# Schemat.net
KiCad netlist of a schematic drawn in EAGLE
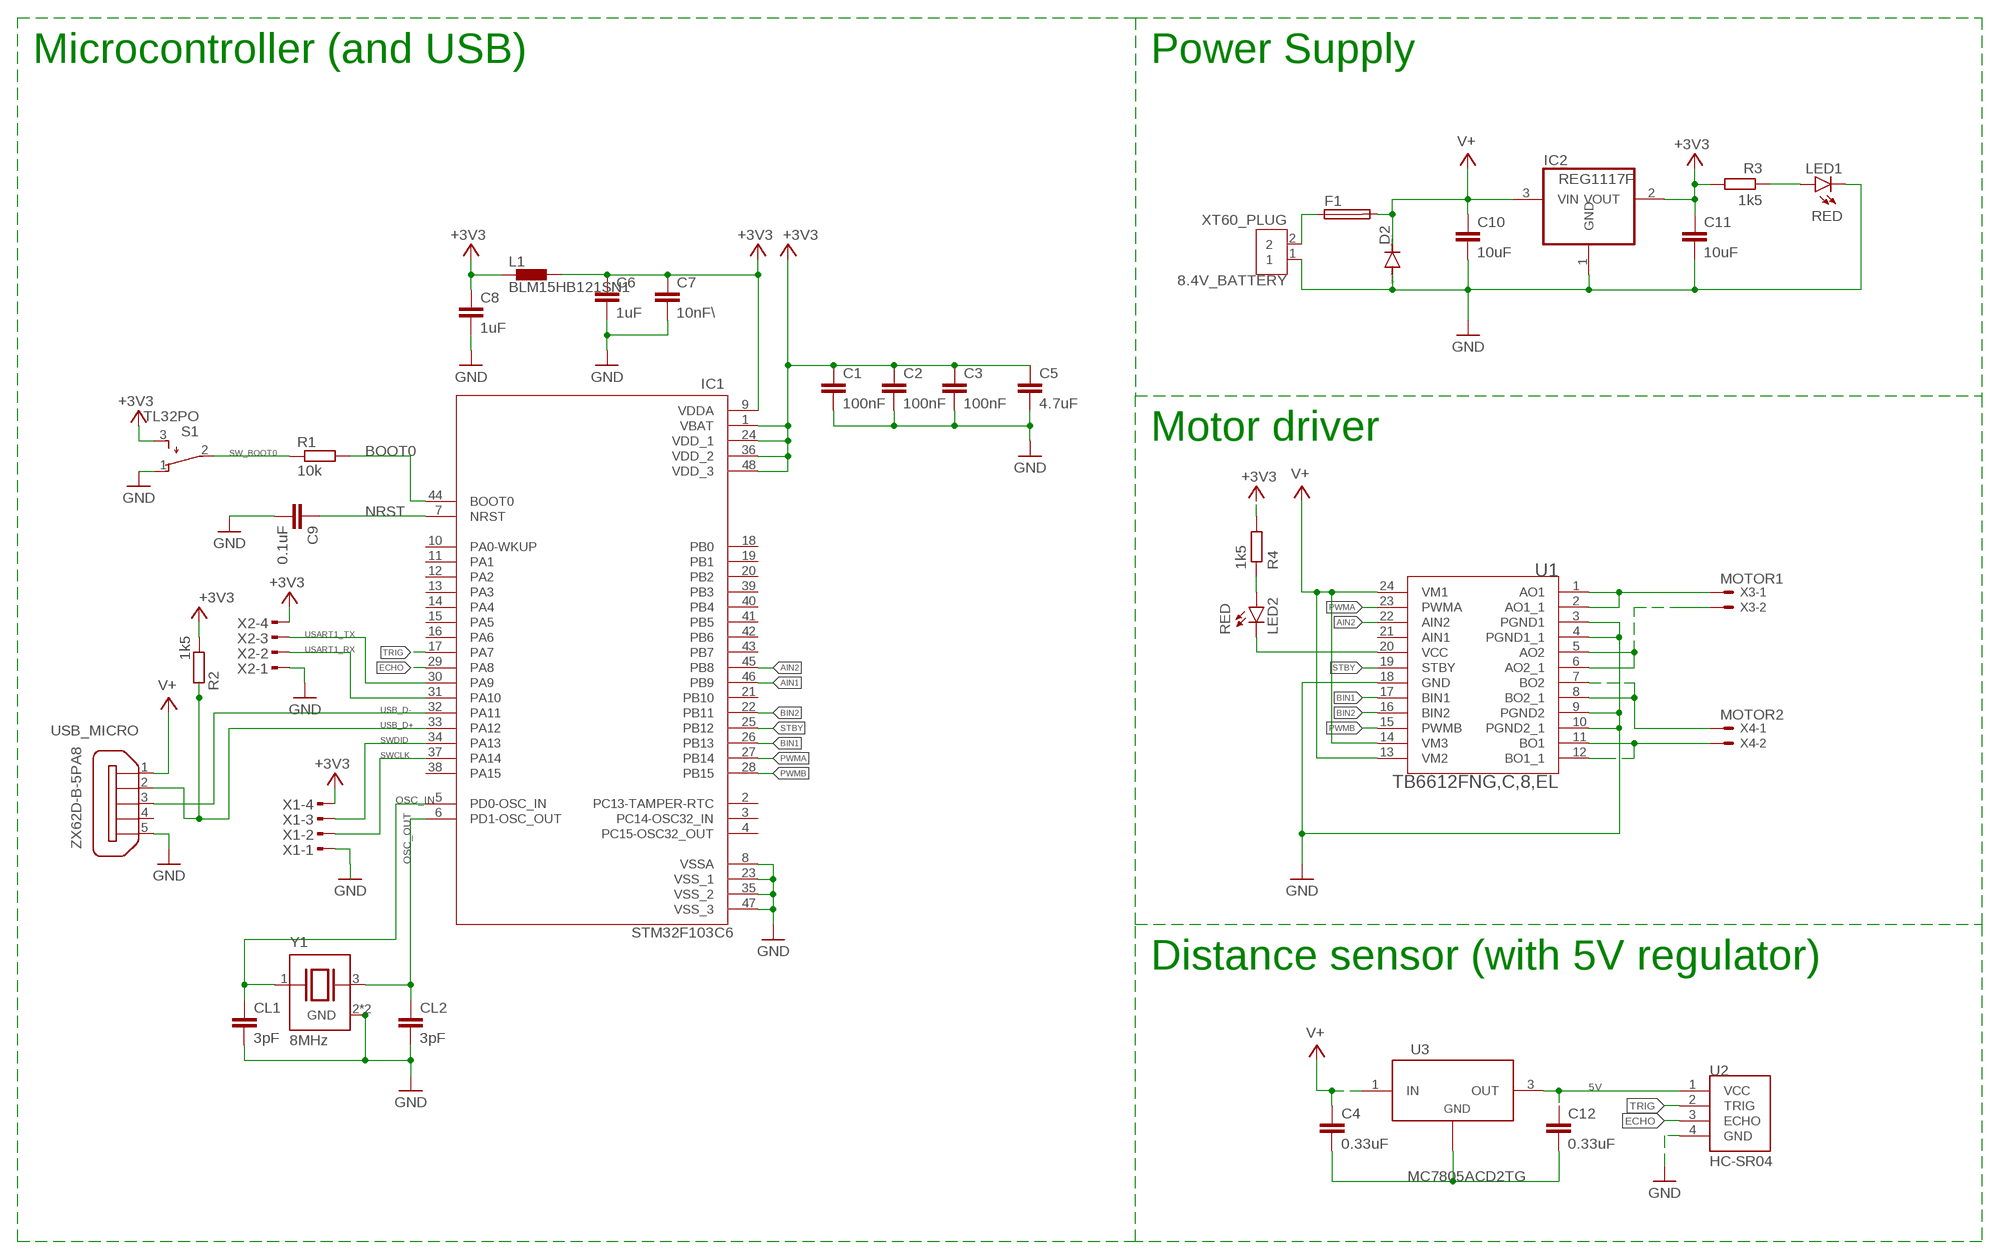
[diagram p0: schematic, sheet 1]

(export (version "E")
  (design (tool "Eeschema 10.0.6"))
  (components
    (comp (ref "8.4V_BATTERY")
      (value "XT60_PLUG")
      (footprint "eagle-import:AMASS_XT60PB-M")
      (fields (field (name "MF") "Pololu") (field (name "MP") "XT60 YELLOW"))
      (libsource (lib "eagle-import") (part "XT60_YELLOW"))
    )
    (comp (ref "C1")
      (value "100nF")
      (footprint "eagle-import:C0805")
      (libsource (lib "eagle-import") (part "C-EUC0805"))
    )
    (comp (ref "C2")
      (value "100nF")
      (footprint "eagle-import:C0805")
      (libsource (lib "eagle-import") (part "C-EUC0805"))
    )
    (comp (ref "C3")
      (value "100nF")
      (footprint "eagle-import:C0805")
      (libsource (lib "eagle-import") (part "C-EUC0805"))
    )
    (comp (ref "C4")
      (value "0.33uF")
      (footprint "eagle-import:C0805")
      (libsource (lib "eagle-import") (part "C-EUC0805"))
    )
    (comp (ref "C5")
      (value "4.7uF")
      (footprint "eagle-import:C0805")
      (libsource (lib "eagle-import") (part "C-EUC0805"))
    )
    (comp (ref "C6")
      (value "1uF")
      (footprint "eagle-import:C0805")
      (libsource (lib "eagle-import") (part "C-EUC0805"))
    )
    (comp (ref "C7")
      (value "10nF\\")
      (footprint "eagle-import:C0805")
      (libsource (lib "eagle-import") (part "C-EUC0805"))
    )
    (comp (ref "C8")
      (value "1uF")
      (footprint "eagle-import:C0805")
      (libsource (lib "eagle-import") (part "C-EUC0805"))
    )
    (comp (ref "C9")
      (value "0.1uF")
      (footprint "eagle-import:C0805")
      (libsource (lib "eagle-import") (part "C-EUC0805"))
    )
    (comp (ref "C10")
      (value "10uF")
      (footprint "eagle-import:C0805")
      (libsource (lib "eagle-import") (part "C-EUC0805"))
    )
    (comp (ref "C11")
      (value "10uF")
      (footprint "eagle-import:C0805")
      (libsource (lib "eagle-import") (part "C-EUC0805"))
    )
    (comp (ref "C12")
      (value "0.33uF")
      (footprint "eagle-import:C0805")
      (libsource (lib "eagle-import") (part "C-EUC0805"))
    )
    (comp (ref "CL1")
      (value "3pF")
      (footprint "eagle-import:C0805")
      (libsource (lib "eagle-import") (part "C-EUC0805"))
    )
    (comp (ref "CL2")
      (value "3pF")
      (footprint "eagle-import:C0805")
      (libsource (lib "eagle-import") (part "C-EUC0805"))
    )
    (comp (ref "D2")
      (value "1N4004")
      (footprint "eagle-import:DO41-10")
      (libsource (lib "eagle-import") (part "1N4004"))
    )
    (comp (ref "F1")
      (value "19559")
      (footprint "eagle-import:19559")
      (fields (field (name "MPN") "55900000001"))
      (libsource (lib "eagle-import") (part "19559"))
    )
    (comp (ref "IC1")
      (value "STM32F103C6")
      (footprint "eagle-import:QFP50P900X900X160-48N")
      (fields (field (name "MANUFACTURER") "ST Microelectronics") (field (name "MPN") "STM32F103C6T7A"))
      (libsource (lib "eagle-import") (part "STM32F103_QFP"))
    )
    (comp (ref "IC2")
      (value "REG1117F")
      (footprint "eagle-import:DD-3")
      (fields (field (name "MF") "TEXAS INSTRUMENTS") (field (name "MPN") "REG1117FAKTTT"))
      (libsource (lib "eagle-import") (part "REG1117F"))
    )
    (comp (ref "L1")
      (value "BLM15HB121SN1")
      (footprint "eagle-import:0402")
      (libsource (lib "eagle-import") (part "BLM15HB121SN1"))
    )
    (comp (ref "LED1")
      (value "RED")
      (footprint "eagle-import:LED3MM")
      (libsource (lib "eagle-import") (part "LED3MM"))
    )
    (comp (ref "LED2")
      (value "RED")
      (footprint "eagle-import:LED3MM")
      (libsource (lib "eagle-import") (part "LED3MM"))
    )
    (comp (ref "R1")
      (value "10k")
      (footprint "eagle-import:0204V")
      (libsource (lib "eagle-import") (part "R-EU_0204/2V"))
    )
    (comp (ref "R2")
      (value "1k5")
      (footprint "eagle-import:0204V")
      (libsource (lib "eagle-import") (part "R-EU_0204/2V"))
    )
    (comp (ref "R3")
      (value "1k5")
      (footprint "eagle-import:R0805")
      (libsource (lib "eagle-import") (part "R-EU_R0805"))
    )
    (comp (ref "R4")
      (value "1k5")
      (footprint "eagle-import:R0805")
      (libsource (lib "eagle-import") (part "R-EU_R0805"))
    )
    (comp (ref "S1")
      (value "TL32PO")
      (footprint "eagle-import:TL3XPO")
      (libsource (lib "eagle-import") (part "TL32PO"))
    )
    (comp (ref "U1")
      (value "TB6612FNG,C,8,EL")
      (footprint "eagle-import:SSOP-24")
      (fields
        (field (name "DIGI-KEY_PART") "TB6612FNGC8ELCT-ND")
        (field (name "MANUFACTURER") "Toshiba Semiconductor and Storage")
        (field (name "CREATED_BY") "PCBLayout.com")
      )
      (libsource (lib "eagle-import") (part "TB6612FNG,C,8,EL"))
    )
    (comp (ref "U2")
      (value "HC-SR04")
      (footprint "eagle-import:XCVR_HC-SR04")
      (fields (field (name "MF") "OSEPP Electronics"))
      (libsource (lib "eagle-import") (part "HC-SR04"))
    )
    (comp (ref "U3")
      (value "MC7805ACD2TG")
      (footprint "eagle-import:D2PAK")
      (fields
        (field (name "DIGIKEY_PART_NUMBER") "MC7805ACD2TGOS-ND")
        (field (name "MANUFACTURER") "ON Semiconductor")
        (field (name "CREATED_BY") "PCBLayout.com")
      )
      (libsource (lib "eagle-import") (part "MC7805ACD2TG"))
    )
    (comp (ref "USB_MICRO")
      (value "ZX62D-B-5PA8")
      (footprint "eagle-import:ZX62D-B-5PA8")
      (fields (field (name "MF") "Hirose"))
      (libsource (lib "eagle-import") (part "ZX62D-B-5PA8"))
    )
    (comp (ref "X1")
      (value "MTOP-4")
      (footprint "eagle-import:MTOP-4")
      (libsource (lib "eagle-import") (part "MTOP-4"))
    )
    (comp (ref "X2")
      (value "MTOP-4")
      (footprint "eagle-import:MTOP-4")
      (libsource (lib "eagle-import") (part "MTOP-4"))
    )
    (comp (ref "X3")
      (value "MOTOR1")
      (footprint "eagle-import:53048-02")
      (fields (field (name "MF") "MOLEX") (field (name "MPN") "53048-0210"))
      (libsource (lib "eagle-import") (part "53?-02048"))
    )
    (comp (ref "X4")
      (value "MOTOR2")
      (footprint "eagle-import:53048-02")
      (fields (field (name "MF") "MOLEX") (field (name "MPN") "53048-0210"))
      (libsource (lib "eagle-import") (part "53?-02048"))
    )
    (comp (ref "Y1")
      (value "8MHz")
      (footprint "eagle-import:XTAL_ABMM2-8.0000MHZ-E1-T")
      (fields (field (name "MF") "Abracon") (field (name "MP") "ABMM2-8.0000MHZ-E1-T"))
      (libsource (lib "eagle-import") (part "ABMM2-8.0000MHZ-E1-T"))
    )
  )
  (nets
    (net (code "1") (name "+3V3") (class "Default")
      (node (ref "C1") (pin "1") (pinfunction "1_1") (pintype "passive"))
      (node (ref "C11") (pin "1") (pinfunction "1_1") (pintype "passive"))
      (node (ref "C2") (pin "1") (pinfunction "1_1") (pintype "passive"))
      (node (ref "C3") (pin "1") (pinfunction "1_1") (pintype "passive"))
      (node (ref "C5") (pin "1") (pinfunction "1_1") (pintype "passive"))
      (node (ref "C6") (pin "1") (pinfunction "1_1") (pintype "passive"))
      (node (ref "C7") (pin "1") (pinfunction "1_1") (pintype "passive"))
      (node (ref "C8") (pin "1") (pinfunction "1_1") (pintype "passive"))
      (node (ref "IC1") (pin "1") (pinfunction "VBAT_1") (pintype "power_in"))
      (node (ref "IC1") (pin "24") (pinfunction "VDD_1_24") (pintype "power_in"))
      (node (ref "IC1") (pin "36") (pinfunction "VDD_2_36") (pintype "power_in"))
      (node (ref "IC1") (pin "48") (pinfunction "VDD_3_48") (pintype "power_in"))
      (node (ref "IC1") (pin "9") (pinfunction "VDDA_9") (pintype "power_in"))
      (node (ref "IC2") (pin "2") (pinfunction "VOUT_2") (pintype "output"))
      (node (ref "L1") (pin "1") (pinfunction "1_1") (pintype "passive"))
      (node (ref "L1") (pin "2") (pinfunction "2_2") (pintype "passive"))
      (node (ref "R2") (pin "2") (pinfunction "2_2") (pintype "passive"))
      (node (ref "R3") (pin "2") (pinfunction "2_2") (pintype "passive"))
      (node (ref "R4") (pin "2") (pinfunction "2_2") (pintype "passive"))
      (node (ref "S1") (pin "3") (pinfunction "S_3") (pintype "passive"))
      (node (ref "X1") (pin "4") (pinfunction "1_4") (pintype "passive"))
      (node (ref "X2") (pin "4") (pinfunction "1_4") (pintype "passive"))
    )
    (net (code "2") (name "/5V") (class "Default")
      (node (ref "C12") (pin "1") (pinfunction "1_1") (pintype "passive"))
      (node (ref "U2") (pin "1") (pinfunction "VCC_1") (pintype "power_in"))
      (node (ref "U3") (pin "3") (pinfunction "OUT_3") (pintype "output"))
    )
    (net (code "3") (name "/BOOT0") (class "Default")
      (node (ref "IC1") (pin "44") (pinfunction "BOOT0_44") (pintype "input"))
      (node (ref "R1") (pin "2") (pinfunction "2_2") (pintype "passive"))
    )
    (net (code "4") (name "/NRST") (class "Default")
      (node (ref "C9") (pin "1") (pinfunction "1_1") (pintype "passive"))
      (node (ref "IC1") (pin "7") (pinfunction "NRST_7") (pintype "bidirectional"))
    )
    (net (code "5") (name "/OSC_IN") (class "Default")
      (node (ref "CL1") (pin "2") (pinfunction "2_2") (pintype "passive"))
      (node (ref "IC1") (pin "5") (pinfunction "PD0-OSC_IN_5") (pintype "bidirectional"))
      (node (ref "Y1") (pin "1") (pinfunction "1_1") (pintype "passive"))
    )
    (net (code "6") (name "/OSC_OUT") (class "Default")
      (node (ref "CL2") (pin "2") (pinfunction "2_2") (pintype "passive"))
      (node (ref "IC1") (pin "6") (pinfunction "PD1-OSC_OUT_6") (pintype "bidirectional"))
      (node (ref "Y1") (pin "3") (pinfunction "2_3") (pintype "passive"))
    )
    (net (code "7") (name "/SWCLK") (class "Default")
      (node (ref "IC1") (pin "37") (pinfunction "PA14_37") (pintype "bidirectional"))
      (node (ref "X1") (pin "2") (pinfunction "1_2") (pintype "passive"))
    )
    (net (code "8") (name "/SWDID") (class "Default")
      (node (ref "IC1") (pin "34") (pinfunction "PA13_34") (pintype "bidirectional"))
      (node (ref "X1") (pin "3") (pinfunction "1_3") (pintype "passive"))
    )
    (net (code "9") (name "/SW_BOOT0") (class "Default")
      (node (ref "R1") (pin "1") (pinfunction "1_1") (pintype "passive"))
      (node (ref "S1") (pin "2") (pinfunction "P_2") (pintype "passive"))
    )
    (net (code "10") (name "/USART1_RX") (class "Default")
      (node (ref "IC1") (pin "31") (pinfunction "PA10_31") (pintype "bidirectional"))
      (node (ref "X2") (pin "2") (pinfunction "1_2") (pintype "passive"))
    )
    (net (code "11") (name "/USART1_TX") (class "Default")
      (node (ref "IC1") (pin "30") (pinfunction "PA9_30") (pintype "bidirectional"))
      (node (ref "X2") (pin "3") (pinfunction "1_3") (pintype "passive"))
    )
    (net (code "12") (name "/USB_D+") (class "Default")
      (node (ref "IC1") (pin "33") (pinfunction "PA12_33") (pintype "bidirectional"))
      (node (ref "R2") (pin "1") (pinfunction "1_1") (pintype "passive"))
      (node (ref "USB_MICRO") (pin "2") (pinfunction "2_2") (pintype "passive"))
    )
    (net (code "13") (name "/USB_D-") (class "Default")
      (node (ref "IC1") (pin "32") (pinfunction "PA11_32") (pintype "bidirectional"))
      (node (ref "USB_MICRO") (pin "3") (pinfunction "3_3") (pintype "passive"))
    )
    (net (code "14") (name "AIN1") (class "Default")
      (node (ref "IC1") (pin "46") (pinfunction "PB9_46") (pintype "bidirectional"))
    )
    (net (code "15") (name "AIN2") (class "Default")
      (node (ref "IC1") (pin "45") (pinfunction "PB8_45") (pintype "bidirectional"))
    )
    (net (code "16") (name "BIN1") (class "Default")
      (node (ref "IC1") (pin "26") (pinfunction "PB13_26") (pintype "bidirectional"))
      (node (ref "U1") (pin "17") (pinfunction "BIN1_17") (pintype "input"))
    )
    (net (code "17") (name "BIN2") (class "Default")
      (node (ref "IC1") (pin "22") (pinfunction "PB11_22") (pintype "bidirectional"))
    )
    (net (code "18") (name "ECHO") (class "Default")
      (node (ref "IC1") (pin "29") (pinfunction "PA8_29") (pintype "bidirectional"))
      (node (ref "U2") (pin "3") (pinfunction "ECHO_3") (pintype "bidirectional"))
    )
    (net (code "19") (name "GND") (class "Default")
      (node (ref "8.4V_BATTERY") (pin "1") (pinfunction "1_1") (pintype "passive"))
      (node (ref "C1") (pin "2") (pinfunction "2_2") (pintype "passive"))
      (node (ref "C10") (pin "2") (pinfunction "2_2") (pintype "passive"))
      (node (ref "C11") (pin "2") (pinfunction "2_2") (pintype "passive"))
      (node (ref "C2") (pin "2") (pinfunction "2_2") (pintype "passive"))
      (node (ref "C3") (pin "2") (pinfunction "2_2") (pintype "passive"))
      (node (ref "C5") (pin "2") (pinfunction "2_2") (pintype "passive"))
      (node (ref "C6") (pin "2") (pinfunction "2_2") (pintype "passive"))
      (node (ref "C7") (pin "2") (pinfunction "2_2") (pintype "passive"))
      (node (ref "C8") (pin "2") (pinfunction "2_2") (pintype "passive"))
      (node (ref "C9") (pin "2") (pinfunction "2_2") (pintype "passive"))
      (node (ref "CL1") (pin "1") (pinfunction "1_1") (pintype "passive"))
      (node (ref "CL2") (pin "1") (pinfunction "1_1") (pintype "passive"))
      (node (ref "D2") (pin "A") (pinfunction "A_A") (pintype "passive"))
      (node (ref "IC1") (pin "23") (pinfunction "VSS_1_23") (pintype "power_in"))
      (node (ref "IC1") (pin "35") (pinfunction "VSS_2_35") (pintype "power_in"))
      (node (ref "IC1") (pin "47") (pinfunction "VSS_3_47") (pintype "power_in"))
      (node (ref "IC1") (pin "8") (pinfunction "VSSA_8") (pintype "power_in"))
      (node (ref "IC2") (pin "1") (pinfunction "GND_1") (pintype "power_in"))
      (node (ref "LED1") (pin "K") (pinfunction "C_K") (pintype "passive"))
      (node (ref "S1") (pin "1") (pinfunction "O_1") (pintype "passive"))
      (node (ref "U1") (pin "10") (pinfunction "PGND2_1_10") (pintype "power_in"))
      (node (ref "U1") (pin "18") (pinfunction "GND_18") (pintype "power_in"))
      (node (ref "U1") (pin "3") (pinfunction "PGND1_3") (pintype "power_in"))
      (node (ref "U1") (pin "4") (pinfunction "PGND1_1_4") (pintype "power_in"))
      (node (ref "U1") (pin "9") (pinfunction "PGND2_9") (pintype "power_in"))
      (node (ref "U2") (pin "4") (pinfunction "GND_4") (pintype "power_in"))
      (node (ref "USB_MICRO") (pin "5") (pinfunction "5_5") (pintype "passive"))
      (node (ref "X1") (pin "1") (pinfunction "1_1") (pintype "passive"))
      (node (ref "X2") (pin "1") (pinfunction "1_1") (pintype "passive"))
      (node (ref "Y1") (pin "2") (pinfunction "GND_2") (pintype "power_in"))
      (node (ref "Y1") (pin "4") (pinfunction "GND_4") (pintype "power_in"))
    )
    (net (code "20") (name "Net-(8.4V_BATTERY-Pad2)") (class "Default")
      (node (ref "8.4V_BATTERY") (pin "2") (pinfunction "2_2") (pintype "passive"))
      (node (ref "F1") (pin "1") (pinfunction "1_1") (pintype "passive"))
    )
    (net (code "21") (name "Net-(LED1-PadA)") (class "Default")
      (node (ref "LED1") (pin "A") (pinfunction "A_A") (pintype "passive"))
      (node (ref "R3") (pin "1") (pinfunction "1_1") (pintype "passive"))
    )
    (net (code "22") (name "Net-(LED2-C)") (class "Default")
      (node (ref "LED2") (pin "K") (pinfunction "C_K") (pintype "passive"))
      (node (ref "U1") (pin "20") (pinfunction "VCC_20") (pintype "power_in"))
    )
    (net (code "23") (name "Net-(LED2-PadA)") (class "Default")
      (node (ref "LED2") (pin "A") (pinfunction "A_A") (pintype "passive"))
      (node (ref "R4") (pin "1") (pinfunction "1_1") (pintype "passive"))
    )
    (net (code "24") (name "Net-(U1-AO1)") (class "Default")
      (node (ref "U1") (pin "1") (pinfunction "AO1_1") (pintype "output"))
      (node (ref "U1") (pin "2") (pinfunction "AO1_1_2") (pintype "output"))
      (node (ref "X3") (pin "1") (pinfunction "S_1") (pintype "passive"))
    )
    (net (code "25") (name "Net-(U1-AO2)") (class "Default")
      (node (ref "U1") (pin "5") (pinfunction "AO2_5") (pintype "output"))
      (node (ref "U1") (pin "6") (pinfunction "AO2_1_6") (pintype "bidirectional"))
      (node (ref "X3") (pin "2") (pinfunction "S_2") (pintype "passive"))
    )
    (net (code "26") (name "Net-(U1-BO1)") (class "Default")
      (node (ref "U1") (pin "11") (pinfunction "BO1_11") (pintype "output"))
      (node (ref "U1") (pin "12") (pinfunction "BO1_1_12") (pintype "output"))
      (node (ref "X4") (pin "2") (pinfunction "S_2") (pintype "passive"))
    )
    (net (code "27") (name "Net-(U1-BO2)") (class "Default")
      (node (ref "U1") (pin "7") (pinfunction "BO2_7") (pintype "output"))
      (node (ref "U1") (pin "8") (pinfunction "BO2_1_8") (pintype "output"))
      (node (ref "X4") (pin "1") (pinfunction "S_1") (pintype "passive"))
    )
    (net (code "28") (name "Net-(U3-ADJ{slash}GND)") (class "Default")
      (node (ref "C12") (pin "2") (pinfunction "2_2") (pintype "passive"))
      (node (ref "C4") (pin "2") (pinfunction "2_2") (pintype "passive"))
      (node (ref "U3") (pin "2") (pinfunction "ADJ/GND_2") (pintype "power_in"))
    )
    (net (code "29") (name "PWMA") (class "Default")
      (node (ref "IC1") (pin "27") (pinfunction "PB14_27") (pintype "bidirectional"))
    )
    (net (code "30") (name "PWMB") (class "Default")
      (node (ref "IC1") (pin "28") (pinfunction "PB15_28") (pintype "bidirectional"))
    )
    (net (code "31") (name "STBY") (class "Default")
      (node (ref "IC1") (pin "25") (pinfunction "PB12_25") (pintype "bidirectional"))
      (node (ref "U1") (pin "19") (pinfunction "STBY_19") (pintype "input"))
    )
    (net (code "32") (name "TRIG") (class "Default")
      (node (ref "IC1") (pin "17") (pinfunction "PA7_17") (pintype "bidirectional"))
      (node (ref "U2") (pin "2") (pinfunction "TRIG_2") (pintype "bidirectional"))
    )
    (net (code "33") (name "V+") (class "Default")
      (node (ref "C10") (pin "1") (pinfunction "1_1") (pintype "passive"))
      (node (ref "C4") (pin "1") (pinfunction "1_1") (pintype "passive"))
      (node (ref "D2") (pin "C") (pinfunction "C_C") (pintype "passive"))
      (node (ref "F1") (pin "2") (pinfunction "2_2") (pintype "passive"))
      (node (ref "IC2") (pin "3") (pinfunction "VIN_3") (pintype "input"))
      (node (ref "U1") (pin "13") (pinfunction "VM2_13") (pintype "passive"))
      (node (ref "U1") (pin "14") (pinfunction "VM3_14") (pintype "bidirectional"))
      (node (ref "U1") (pin "24") (pinfunction "VM1_24") (pintype "passive"))
      (node (ref "U3") (pin "1") (pinfunction "IN_1") (pintype "input"))
      (node (ref "USB_MICRO") (pin "1") (pinfunction "1_1") (pintype "passive"))
    )
    (net (code "34") (name "unconnected-(IC1-PA0-WKUP-Pad10)") (class "Default")
      (node (ref "IC1") (pin "10") (pinfunction "PA0-WKUP_10") (pintype "bidirectional"))
    )
    (net (code "35") (name "unconnected-(IC1-PA1-Pad11)") (class "Default")
      (node (ref "IC1") (pin "11") (pinfunction "PA1_11") (pintype "bidirectional"))
    )
    (net (code "36") (name "unconnected-(IC1-PA2-Pad12)") (class "Default")
      (node (ref "IC1") (pin "12") (pinfunction "PA2_12") (pintype "bidirectional"))
    )
    (net (code "37") (name "unconnected-(IC1-PA3-Pad13)") (class "Default")
      (node (ref "IC1") (pin "13") (pinfunction "PA3_13") (pintype "bidirectional"))
    )
    (net (code "38") (name "unconnected-(IC1-PA4-Pad14)") (class "Default")
      (node (ref "IC1") (pin "14") (pinfunction "PA4_14") (pintype "bidirectional"))
    )
    (net (code "39") (name "unconnected-(IC1-PA5-Pad15)") (class "Default")
      (node (ref "IC1") (pin "15") (pinfunction "PA5_15") (pintype "bidirectional"))
    )
    (net (code "40") (name "unconnected-(IC1-PA6-Pad16)") (class "Default")
      (node (ref "IC1") (pin "16") (pinfunction "PA6_16") (pintype "bidirectional"))
    )
    (net (code "41") (name "unconnected-(IC1-PA15-Pad38)") (class "Default")
      (node (ref "IC1") (pin "38") (pinfunction "PA15_38") (pintype "bidirectional"))
    )
    (net (code "42") (name "unconnected-(IC1-PB0-Pad18)") (class "Default")
      (node (ref "IC1") (pin "18") (pinfunction "PB0_18") (pintype "bidirectional"))
    )
    (net (code "43") (name "unconnected-(IC1-PB1-Pad19)") (class "Default")
      (node (ref "IC1") (pin "19") (pinfunction "PB1_19") (pintype "bidirectional"))
    )
    (net (code "44") (name "unconnected-(IC1-PB2-Pad20)") (class "Default")
      (node (ref "IC1") (pin "20") (pinfunction "PB2_20") (pintype "bidirectional"))
    )
    (net (code "45") (name "unconnected-(IC1-PB3-Pad39)") (class "Default")
      (node (ref "IC1") (pin "39") (pinfunction "PB3_39") (pintype "bidirectional"))
    )
    (net (code "46") (name "unconnected-(IC1-PB4-Pad40)") (class "Default")
      (node (ref "IC1") (pin "40") (pinfunction "PB4_40") (pintype "bidirectional"))
    )
    (net (code "47") (name "unconnected-(IC1-PB5-Pad41)") (class "Default")
      (node (ref "IC1") (pin "41") (pinfunction "PB5_41") (pintype "bidirectional"))
    )
    (net (code "48") (name "unconnected-(IC1-PB6-Pad42)") (class "Default")
      (node (ref "IC1") (pin "42") (pinfunction "PB6_42") (pintype "bidirectional"))
    )
    (net (code "49") (name "unconnected-(IC1-PB7-Pad43)") (class "Default")
      (node (ref "IC1") (pin "43") (pinfunction "PB7_43") (pintype "bidirectional"))
    )
    (net (code "50") (name "unconnected-(IC1-PB10-Pad21)") (class "Default")
      (node (ref "IC1") (pin "21") (pinfunction "PB10_21") (pintype "bidirectional"))
    )
    (net (code "51") (name "unconnected-(IC1-PC13-TAMPER-RTC-Pad2)") (class "Default")
      (node (ref "IC1") (pin "2") (pinfunction "PC13-TAMPER-RTC_2") (pintype "bidirectional"))
    )
    (net (code "52") (name "unconnected-(IC1-PC14-OSC32_IN-Pad3)") (class "Default")
      (node (ref "IC1") (pin "3") (pinfunction "PC14-OSC32_IN_3") (pintype "bidirectional"))
    )
    (net (code "53") (name "unconnected-(IC1-PC15-OSC32_OUT-Pad4)") (class "Default")
      (node (ref "IC1") (pin "4") (pinfunction "PC15-OSC32_OUT_4") (pintype "bidirectional"))
    )
    (net (code "54") (name "unconnected-(U1-AIN1-Pad21)") (class "Default")
      (node (ref "U1") (pin "21") (pinfunction "AIN1_21") (pintype "input"))
    )
    (net (code "55") (name "unconnected-(U1-AIN2-Pad22)") (class "Default")
      (node (ref "U1") (pin "22") (pinfunction "AIN2_22") (pintype "input"))
    )
    (net (code "56") (name "unconnected-(U1-BIN2-Pad16)") (class "Default")
      (node (ref "U1") (pin "16") (pinfunction "BIN2_16") (pintype "input"))
    )
    (net (code "57") (name "unconnected-(U1-PWMA-Pad23)") (class "Default")
      (node (ref "U1") (pin "23") (pinfunction "PWMA_23") (pintype "input"))
    )
    (net (code "58") (name "unconnected-(U1-PWMB-Pad15)") (class "Default")
      (node (ref "U1") (pin "15") (pinfunction "PWMB_15") (pintype "input"))
    )
    (net (code "59") (name "unconnected-(USB_MICRO-Pad4)") (class "Default")
      (node (ref "USB_MICRO") (pin "4") (pinfunction "4_4") (pintype "passive"))
    )
  )
)
